# SEP00755AG.net
KiCad netlist of a schematic drawn in Altium Designer
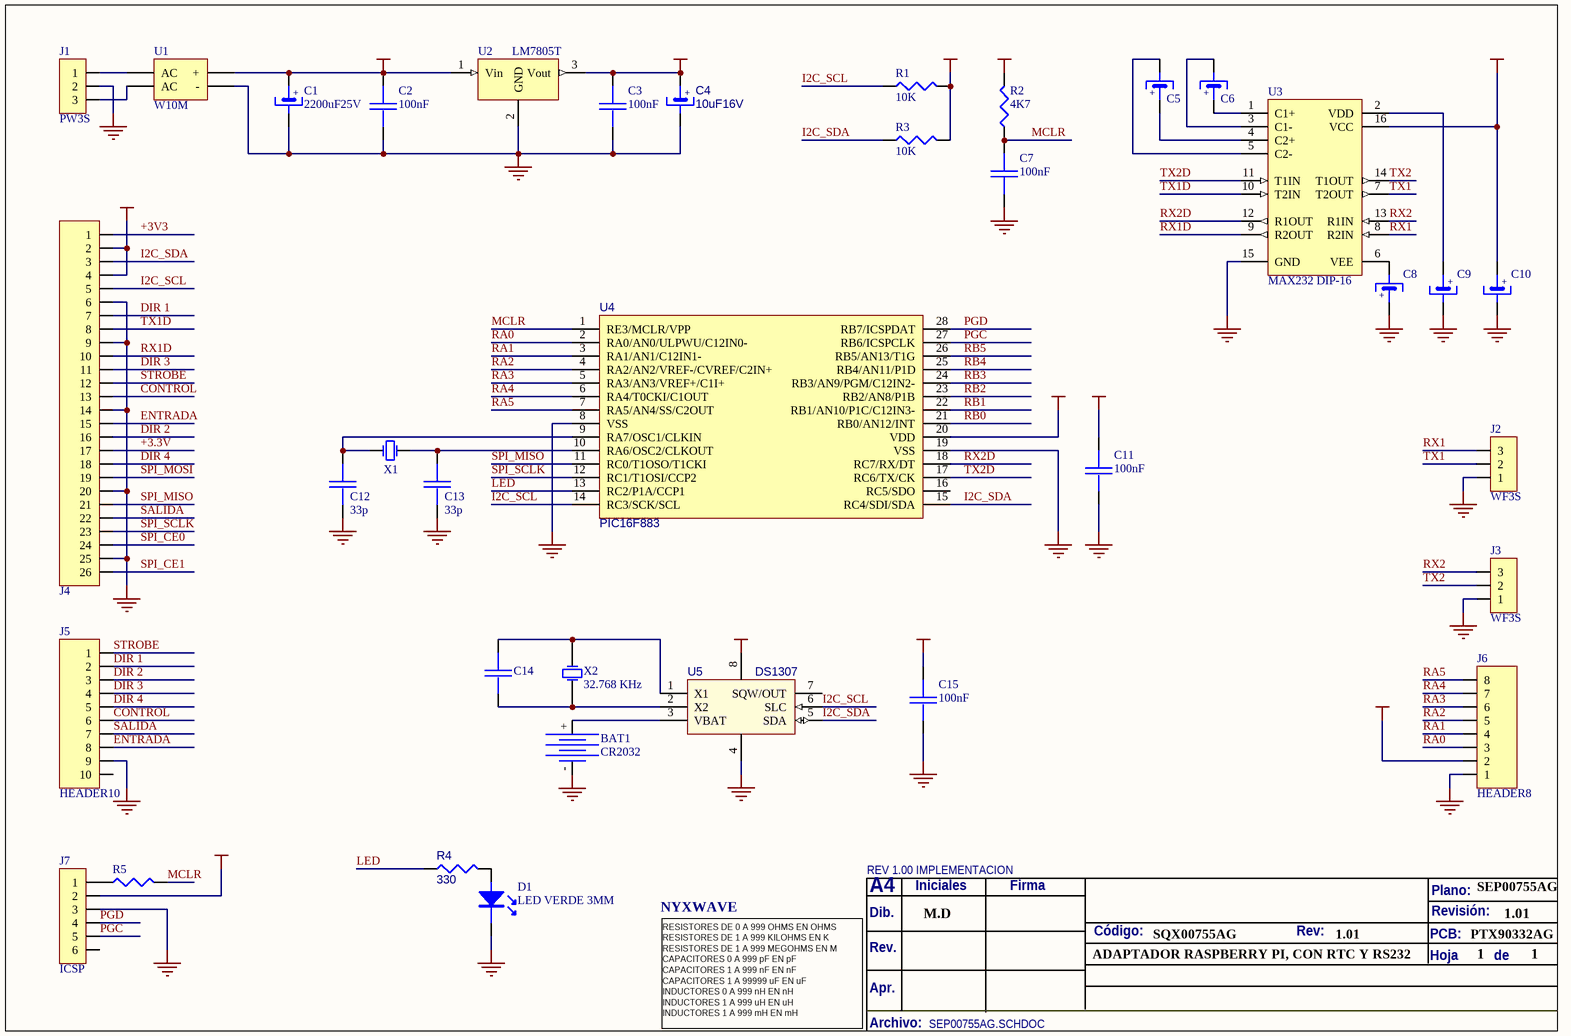
[diagram p0: SEP00755AG.SCHDOC]

(export (version "E")
  (design (tool "Eeschema 10.0.6"))
  (components
    (comp (ref "BAT1")
      (value "CR2032")
      (footprint "CR2032 HOLDER")
      (description "CR2032 BATTERY HOLDER")
      (libsource (lib "ACCESORIOS DE MONTAJE") (part "CR2032 HOLDER"))
    )
    (comp (ref "C1")
      (value "2200uF25V")
      (footprint "CE 7.5/16.0")
      (description "CAPACITOR ELECTROLITICO RADIAL 16X25 mm PASO 7.5 mm +/-20% 85ºC 25V 2200uF")
      (libsource (lib "CAPACITORES ELECTROLITICOS") (part "2200uF25V"))
    )
    (comp (ref "C2")
      (value "100nF")
      (footprint "0805")
      (description "CAPACITOR SMD 0805 X7R  50 V 100 nF")
      (libsource (lib "CAPACITORES SMD0805") (part "100n"))
    )
    (comp (ref "C3")
      (value "100nF")
      (footprint "0805")
      (description "CAPACITOR SMD 0805 X7R  50 V 100 nF")
      (libsource (lib "CAPACITORES SMD0805") (part "100n"))
    )
    (comp (ref "C4")
      (value "10uF16V")
      (footprint "CE 2.5/5.0")
      (description "CAPACITOR ELECTROLITICO RADIAL 5X11mm PASO 2mm 85ªC +/-20 16V 10uF")
      (libsource (lib "CAPACITORES ELECTROLITICOS") (part "10uF16V"))
    )
    (comp (ref "C5")
      (value "10uF50V")
      (footprint "CE 2.5/5.0")
      (description "CAPACITOR ELECTROLITICO RADIAL 5 X11mm PASO 2 mm 85ºC +/-20% 50 V 10 uF")
      (libsource (lib "CAPACITORES ELECTROLITICOS") (part "10uF50V"))
    )
    (comp (ref "C6")
      (value "10uF50V")
      (footprint "CE 2.5/5.0")
      (description "CAPACITOR ELECTROLITICO RADIAL 5 X11mm PASO 2 mm 85ºC +/-20% 50 V 10 uF")
      (libsource (lib "CAPACITORES ELECTROLITICOS") (part "10uF50V"))
    )
    (comp (ref "C7")
      (value "100nF")
      (footprint "0805")
      (description "CAPACITOR SMD 0805 X7R  50 V 100 nF")
      (libsource (lib "CAPACITORES SMD0805") (part "100n"))
    )
    (comp (ref "C8")
      (value "10uF50V")
      (footprint "CE 2.5/5.0")
      (description "CAPACITOR ELECTROLITICO RADIAL 5 X11mm PASO 2 mm 85ºC +/-20% 50 V 10 uF")
      (libsource (lib "CAPACITORES ELECTROLITICOS") (part "10uF50V"))
    )
    (comp (ref "C9")
      (value "10uF50V")
      (footprint "CE 2.5/5.0")
      (description "CAPACITOR ELECTROLITICO RADIAL 5 X11mm PASO 2 mm 85ºC +/-20% 50 V 10 uF")
      (libsource (lib "CAPACITORES ELECTROLITICOS") (part "10uF50V"))
    )
    (comp (ref "C10")
      (value "10uF50V")
      (footprint "CE 2.5/5.0")
      (description "CAPACITOR ELECTROLITICO RADIAL 5 X11mm PASO 2 mm 85ºC +/-20% 50 V 10 uF")
      (libsource (lib "CAPACITORES ELECTROLITICOS") (part "10uF50V"))
    )
    (comp (ref "C11")
      (value "100nF")
      (footprint "0805")
      (description "CAPACITOR SMD 0805 X7R  50 V 100 nF")
      (libsource (lib "CAPACITORES SMD0805") (part "100n"))
    )
    (comp (ref "C12")
      (value "33p")
      (footprint "CAP2.54")
      (description "CAPACITOR PLATE NP0 100V PASO 2.54 mm 33 pF")
      (libsource (lib "CAPACITORES PLATE NP0") (part "33p"))
    )
    (comp (ref "C13")
      (value "33p")
      (footprint "CAP2.54")
      (description "CAPACITOR PLATE NP0 100V PASO 2.54 mm 33 pF")
      (libsource (lib "CAPACITORES PLATE NP0") (part "33p"))
    )
    (comp (ref "C14")
      (value "15p")
      (footprint "CAP2.54")
      (description "CAPACITOR CERAMICO DISCO 2.54 mm  X7R  50V  15pF")
      (libsource (lib "CAPACITORES CERAMICO DISCO") (part "15p"))
    )
    (comp (ref "C15")
      (value "100nF")
      (footprint "0805")
      (description "CAPACITOR SMD 0805 X7R  50 V 100 nF")
      (libsource (lib "CAPACITORES SMD0805") (part "100n"))
    )
    (comp (ref "D1")
      (value "LED VERDE 3MM")
      (footprint "LED 3MM")
      (libsource (lib "DIODOS") (part "LED VERDE 3MM"))
    )
    (comp (ref "J1")
      (value "PW3S")
      (footprint "PW3S")
      (description "PW3S HEADER .156\" RECTO 3 VIAS")
      (libsource (lib "CONECTORES") (part "PW3S"))
    )
    (comp (ref "J2")
      (value "WF3S")
      (footprint "WF3S")
      (description "WF3S HEADER .100\" RECTO 3 VIAS")
      (libsource (lib "CONECTORES") (part "WF3S"))
    )
    (comp (ref "J3")
      (value "WF3S")
      (footprint "WF3S")
      (description "WF3S HEADER .100\" RECTO 3 VIAS")
      (libsource (lib "CONECTORES") (part "WF3S"))
    )
    (comp (ref "J4")
      (value "HEADER26")
      (footprint "IDC26")
      (description "CONECTOR IDC MACHO PCB NO POLARIZADO PASO 2.54 mm RECTO 2X13 VIAS")
      (libsource (lib "CONECTORES") (part "HEADER26"))
    )
    (comp (ref "J5")
      (value "HEADER10")
      (footprint "IDC10")
      (description "CONECTOR IDC MACHO PCB NO POLARIZADO PASO 2.54 mm RECTO 2X5 VIAS")
      (libsource (lib "CONECTORES") (part "HEADER10"))
    )
    (comp (ref "J6")
      (value "HEADER8")
      (footprint "IDC8")
      (description "CONECTOR IDC MACHO PCB NO POLARIZADO PASO 2.54 mm RECTO 2X4 VIAS")
      (libsource (lib "CONECTORES") (part "HEADER8"))
    )
    (comp (ref "J7")
      (value "ICSP")
      (footprint "ICSP")
      (description "TIRA MOLEX 1X6 11MM MACHO RECTA PARA PCB")
      (libsource (lib "CONECTORES") (part "ICSP"))
    )
    (comp (ref "NYXWAVE")
      (value "LOGO NYX")
      (footprint "LOGO_NYX")
      (description "LOGO DE NYXWAVE")
      (libsource (lib "ACCESORIOS DE MONTAJE") (part "LOGO NYXWAVE"))
    )
    (comp (ref "R1")
      (value "10K")
      (footprint "0805")
      (description "RESISTOR SMD0805 0.125 W 5%  10 K OHMS")
      (libsource (lib "RESISTORES SMD0805") (part "10K"))
    )
    (comp (ref "R2")
      (value "4K7")
      (footprint "0805")
      (description "RESISTOR SMD0805 0.125 W 5%  4.7 K OHMS")
      (libsource (lib "RESISTORES SMD0805") (part "4K7"))
    )
    (comp (ref "R3")
      (value "10K")
      (footprint "0805")
      (description "RESISTOR SMD0805 0.125 W 5%  10 K OHMS")
      (libsource (lib "RESISTORES SMD0805") (part "10K"))
    )
    (comp (ref "R4")
      (value "330")
      (footprint "0805")
      (description "RESISTOR SMD0805 0.125 W 5%  330 OHMS")
      (libsource (lib "RESISTORES SMD0805") (part "330"))
    )
    (comp (ref "R5")
      (value "100")
      (footprint "0805")
      (description "RESISTOR SMD0805 0.125 W 5%  100 OHMS")
      (libsource (lib "RESISTORES SMD0805") (part "100"))
    )
    (comp (ref "U1")
      (value "W10M")
      (footprint "CASE22")
      (description "W10M CASE22 CIRC INT RECTIFICADOR PUENTE 1000V 1A")
      (libsource (lib "CIRCUITOS INTEGRADOS DIP") (part "W10M"))
    )
    (comp (ref "U2")
      (value "LM7805T")
      (footprint "TO-220_2")
      (description "LM7805T TO-220 CIRC INT")
      (libsource (lib "CIRCUITOS INTEGRADOS DIP") (part "LM7805T"))
    )
    (comp (ref "U3")
      (value "MAX232 DIP-16")
      (footprint "DIP16")
      (description "MAX232 DIP-16 CIRCUITO INTEGRADO")
      (libsource (lib "Maxim Communication Transceiver") (part "MAX232 DIP-16"))
    )
    (comp (ref "U4")
      (value "PIC16F883")
      (footprint "SOIC 28")
      (description "PIC16F8883 -I/SO SOIC 28 PINES")
      (libsource (lib "CIRCUITOS INTEGRADOS SMD") (part "PIC16F883 SOIC28"))
    )
    (comp (ref "U5")
      (value "DS1307")
      (footprint "SO-8")
      (description "DS1307 SOIC8 CIRCUITO INTEGRADO")
      (libsource (lib "CIRCUITOS INTEGRADOS SMD") (part "DS1307"))
    )
    (comp (ref "X1")
      (value "XL20M-UM5")
      (footprint "UM5")
      (description "XL20M-UM5 CRISTAL DE 20 MHZ 10ppm")
      (libsource (lib "CRISTALES") (part "XL20M-UM5"))
    )
    (comp (ref "X2")
      (value "32.768 KHz")
      (footprint "XTAL ACOSTADO")
      (description "32.768 KHz CRISTAL CILINDRICO")
      (libsource (lib "CRISTALES") (part "32.768 KHz"))
    )
  )
  (nets
    (net (code "1") (name "+5V") (class "Default")
      (node (ref "C10") (pin "1") (pinfunction "1_1") (pintype "passive"))
      (node (ref "C11") (pin "2") (pintype "passive"))
      (node (ref "C15") (pin "2") (pintype "passive"))
      (node (ref "C3") (pin "2") (pintype "passive"))
      (node (ref "C4") (pin "1") (pinfunction "1_1") (pintype "passive"))
      (node (ref "J4") (pin "2") (pinfunction "2_2") (pintype "passive"))
      (node (ref "J4") (pin "4") (pinfunction "4_4") (pintype "passive"))
      (node (ref "J6") (pin "2") (pinfunction "2_2") (pintype "passive"))
      (node (ref "J7") (pin "2") (pinfunction "2_2") (pintype "passive"))
      (node (ref "R1") (pin "2") (pintype "passive"))
      (node (ref "R2") (pin "2") (pintype "passive"))
      (node (ref "R3") (pin "2") (pintype "passive"))
      (node (ref "U2") (pin "3") (pinfunction "Vout_3") (pintype "output"))
      (node (ref "U3") (pin "16") (pinfunction "VCC_16") (pintype "power_in"))
      (node (ref "U4") (pin "20") (pinfunction "VDD_20") (pintype "passive"))
      (node (ref "U5") (pin "8") (pinfunction "VCC_8") (pintype "power_in"))
    )
    (net (code "2") (name "/+3.3V") (class "Default")
      (node (ref "J4") (pin "17") (pinfunction "17_17") (pintype "passive"))
    )
    (net (code "3") (name "/+3V3") (class "Default")
      (node (ref "J4") (pin "1") (pinfunction "1_1") (pintype "passive"))
    )
    (net (code "4") (name "/CONTROL") (class "Default")
      (node (ref "J4") (pin "13") (pinfunction "13_13") (pintype "passive"))
      (node (ref "J5") (pin "6") (pinfunction "6_6") (pintype "passive"))
    )
    (net (code "5") (name "/DIR 1") (class "Default")
      (node (ref "J4") (pin "7") (pinfunction "7_7") (pintype "passive"))
      (node (ref "J5") (pin "2") (pinfunction "2_2") (pintype "passive"))
    )
    (net (code "6") (name "/DIR 2") (class "Default")
      (node (ref "J4") (pin "16") (pinfunction "16_16") (pintype "passive"))
      (node (ref "J5") (pin "3") (pinfunction "3_3") (pintype "passive"))
    )
    (net (code "7") (name "/DIR 3") (class "Default")
      (node (ref "J4") (pin "11") (pinfunction "11_11") (pintype "passive"))
      (node (ref "J5") (pin "4") (pinfunction "4_4") (pintype "passive"))
    )
    (net (code "8") (name "/DIR 4") (class "Default")
      (node (ref "J4") (pin "18") (pinfunction "18_18") (pintype "passive"))
      (node (ref "J5") (pin "5") (pinfunction "5_5") (pintype "passive"))
    )
    (net (code "9") (name "/ENTRADA") (class "Default")
      (node (ref "J4") (pin "15") (pinfunction "15_15") (pintype "passive"))
      (node (ref "J5") (pin "8") (pinfunction "8_8") (pintype "passive"))
    )
    (net (code "10") (name "/I2C_SCL") (class "Default")
      (node (ref "J4") (pin "5") (pinfunction "5_5") (pintype "passive"))
      (node (ref "R1") (pin "1") (pintype "passive"))
      (node (ref "U4") (pin "14") (pinfunction "RC3/SCK/SCL_14") (pintype "passive"))
      (node (ref "U5") (pin "6") (pinfunction "SLC_6") (pintype "input"))
    )
    (net (code "11") (name "/I2C_SDA") (class "Default")
      (node (ref "J4") (pin "3") (pinfunction "3_3") (pintype "passive"))
      (node (ref "R3") (pin "1") (pintype "passive"))
      (node (ref "U4") (pin "15") (pinfunction "RC4/SDI/SDA_15") (pintype "passive"))
      (node (ref "U5") (pin "5") (pinfunction "SDA_5") (pintype "bidirectional"))
    )
    (net (code "12") (name "/LED") (class "Default")
      (node (ref "R4") (pin "1") (pintype "passive"))
      (node (ref "U4") (pin "13") (pinfunction "RC2/P1A/CCP1_13") (pintype "passive"))
    )
    (net (code "13") (name "/MCLR") (class "Default")
      (node (ref "C7") (pin "1") (pintype "passive"))
      (node (ref "R2") (pin "1") (pintype "passive"))
      (node (ref "R5") (pin "1") (pintype "passive"))
      (node (ref "U4") (pin "1") (pinfunction "RE3/MCLR/VPP_1") (pintype "passive"))
    )
    (net (code "14") (name "/PGC") (class "Default")
      (node (ref "J7") (pin "5") (pinfunction "5_5") (pintype "passive"))
      (node (ref "U4") (pin "27") (pinfunction "RB6/ICSPCLK_27") (pintype "passive"))
    )
    (net (code "15") (name "/PGD") (class "Default")
      (node (ref "J7") (pin "4") (pinfunction "4_4") (pintype "passive"))
      (node (ref "U4") (pin "28") (pinfunction "RB7/ICSPDAT_28") (pintype "passive"))
    )
    (net (code "16") (name "/RA0") (class "Default")
      (node (ref "J6") (pin "3") (pinfunction "3_3") (pintype "passive"))
      (node (ref "U4") (pin "2") (pinfunction "RA0/AN0/ULPWU/C12IN0-_2") (pintype "passive"))
    )
    (net (code "17") (name "/RA1") (class "Default")
      (node (ref "J6") (pin "4") (pinfunction "4_4") (pintype "passive"))
      (node (ref "U4") (pin "3") (pinfunction "RA1/AN1/C12IN1-_3") (pintype "passive"))
    )
    (net (code "18") (name "/RA2") (class "Default")
      (node (ref "J6") (pin "5") (pinfunction "5_5") (pintype "passive"))
      (node (ref "U4") (pin "4") (pinfunction "RA2/AN2/VREF-/CVREF/C2IN+_4") (pintype "passive"))
    )
    (net (code "19") (name "/RA3") (class "Default")
      (node (ref "J6") (pin "6") (pinfunction "6_6") (pintype "passive"))
      (node (ref "U4") (pin "5") (pinfunction "RA3/AN3/VREF+/C1I+_5") (pintype "passive"))
    )
    (net (code "20") (name "/RA4") (class "Default")
      (node (ref "J6") (pin "7") (pinfunction "7_7") (pintype "passive"))
      (node (ref "U4") (pin "6") (pinfunction "RA4/T0CKI/C1OUT_6") (pintype "passive"))
    )
    (net (code "21") (name "/RA5") (class "Default")
      (node (ref "J6") (pin "8") (pinfunction "8_8") (pintype "passive"))
      (node (ref "U4") (pin "7") (pinfunction "RA5/AN4/SS/C2OUT_7") (pintype "passive"))
    )
    (net (code "22") (name "/RB0") (class "Default")
      (node (ref "U4") (pin "21") (pinfunction "RB0/AN12/INT_21") (pintype "passive"))
    )
    (net (code "23") (name "/RB1") (class "Default")
      (node (ref "U4") (pin "22") (pinfunction "RB1/AN10/P1C/C12IN3-_22") (pintype "passive"))
    )
    (net (code "24") (name "/RB2") (class "Default")
      (node (ref "U4") (pin "23") (pinfunction "RB2/AN8/P1B_23") (pintype "passive"))
    )
    (net (code "25") (name "/RB3") (class "Default")
      (node (ref "U4") (pin "24") (pinfunction "RB3/AN9/PGM/C12IN2-_24") (pintype "passive"))
    )
    (net (code "26") (name "/RB4") (class "Default")
      (node (ref "U4") (pin "25") (pinfunction "RB4/AN11/P1D_25") (pintype "passive"))
    )
    (net (code "27") (name "/RB5") (class "Default")
      (node (ref "U4") (pin "26") (pinfunction "RB5/AN13/T1G_26") (pintype "passive"))
    )
    (net (code "28") (name "/RX1") (class "Default")
      (node (ref "J2") (pin "3") (pinfunction "3_3") (pintype "passive"))
      (node (ref "U3") (pin "8") (pinfunction "R2IN_8") (pintype "input"))
    )
    (net (code "29") (name "/RX1D") (class "Default")
      (node (ref "J4") (pin "10") (pinfunction "10_10") (pintype "passive"))
      (node (ref "U3") (pin "9") (pinfunction "R2OUT_9") (pintype "output"))
    )
    (net (code "30") (name "/RX2") (class "Default")
      (node (ref "J3") (pin "3") (pinfunction "3_3") (pintype "passive"))
      (node (ref "U3") (pin "13") (pinfunction "R1IN_13") (pintype "input"))
    )
    (net (code "31") (name "/RX2D") (class "Default")
      (node (ref "U3") (pin "12") (pinfunction "R1OUT_12") (pintype "output"))
      (node (ref "U4") (pin "18") (pinfunction "RC7/RX/DT_18") (pintype "passive"))
    )
    (net (code "32") (name "/SALIDA") (class "Default")
      (node (ref "J4") (pin "22") (pinfunction "22_22") (pintype "passive"))
      (node (ref "J5") (pin "7") (pinfunction "7_7") (pintype "passive"))
    )
    (net (code "33") (name "/SPI_CE0") (class "Default")
      (node (ref "J4") (pin "24") (pinfunction "24_24") (pintype "passive"))
    )
    (net (code "34") (name "/SPI_CE1") (class "Default")
      (node (ref "J4") (pin "26") (pinfunction "26_26") (pintype "passive"))
    )
    (net (code "35") (name "/SPI_MISO") (class "Default")
      (node (ref "J4") (pin "21") (pinfunction "21_21") (pintype "passive"))
      (node (ref "U4") (pin "11") (pinfunction "RC0/T1OSO/T1CKI_11") (pintype "passive"))
    )
    (net (code "36") (name "/SPI_MOSI") (class "Default")
      (node (ref "J4") (pin "19") (pinfunction "19_19") (pintype "passive"))
    )
    (net (code "37") (name "/SPI_SCLK") (class "Default")
      (node (ref "J4") (pin "23") (pinfunction "23_23") (pintype "passive"))
      (node (ref "U4") (pin "12") (pinfunction "RC1/T1OSI/CCP2_12") (pintype "passive"))
    )
    (net (code "38") (name "/STROBE") (class "Default")
      (node (ref "J4") (pin "12") (pinfunction "12_12") (pintype "passive"))
      (node (ref "J5") (pin "1") (pinfunction "1_1") (pintype "passive"))
    )
    (net (code "39") (name "/TX1") (class "Default")
      (node (ref "J2") (pin "2") (pinfunction "2_2") (pintype "passive"))
      (node (ref "U3") (pin "7") (pinfunction "T2OUT_7") (pintype "output"))
    )
    (net (code "40") (name "/TX1D") (class "Default")
      (node (ref "J4") (pin "8") (pinfunction "8_8") (pintype "passive"))
      (node (ref "U3") (pin "10") (pinfunction "T2IN_10") (pintype "input"))
    )
    (net (code "41") (name "/TX2") (class "Default")
      (node (ref "J3") (pin "2") (pinfunction "2_2") (pintype "passive"))
      (node (ref "U3") (pin "14") (pinfunction "T1OUT_14") (pintype "output"))
    )
    (net (code "42") (name "/TX2D") (class "Default")
      (node (ref "U3") (pin "11") (pinfunction "T1IN_11") (pintype "input"))
      (node (ref "U4") (pin "17") (pinfunction "RC6/TX/CK_17") (pintype "passive"))
    )
    (net (code "43") (name "GND") (class "Default")
      (node (ref "BAT1") (pin "-") (pinfunction "-_-") (pintype "passive"))
      (node (ref "C1") (pin "2") (pinfunction "2_2") (pintype "passive"))
      (node (ref "C10") (pin "2") (pinfunction "2_2") (pintype "passive"))
      (node (ref "C11") (pin "1") (pintype "passive"))
      (node (ref "C12") (pin "1") (pintype "passive"))
      (node (ref "C13") (pin "1") (pintype "passive"))
      (node (ref "C15") (pin "1") (pintype "passive"))
      (node (ref "C2") (pin "1") (pintype "passive"))
      (node (ref "C3") (pin "1") (pintype "passive"))
      (node (ref "C4") (pin "2") (pinfunction "2_2") (pintype "passive"))
      (node (ref "C7") (pin "2") (pintype "passive"))
      (node (ref "C8") (pin "1") (pinfunction "1_1") (pintype "passive"))
      (node (ref "C9") (pin "2") (pinfunction "2_2") (pintype "passive"))
      (node (ref "D1") (pin "K") (pinfunction "K_K") (pintype "passive"))
      (node (ref "J1") (pin "2") (pinfunction "2_2") (pintype "passive"))
      (node (ref "J2") (pin "1") (pinfunction "1_1") (pintype "passive"))
      (node (ref "J3") (pin "1") (pinfunction "1_1") (pintype "passive"))
      (node (ref "J4") (pin "14") (pinfunction "14_14") (pintype "passive"))
      (node (ref "J4") (pin "20") (pinfunction "20_20") (pintype "passive"))
      (node (ref "J4") (pin "25") (pinfunction "25_25") (pintype "passive"))
      (node (ref "J4") (pin "6") (pinfunction "6_6") (pintype "passive"))
      (node (ref "J4") (pin "9") (pinfunction "9_9") (pintype "passive"))
      (node (ref "J5") (pin "9") (pinfunction "9_9") (pintype "passive"))
      (node (ref "J6") (pin "1") (pinfunction "1_1") (pintype "passive"))
      (node (ref "J7") (pin "3") (pinfunction "3_3") (pintype "passive"))
      (node (ref "U1") (pin "3") (pinfunction "-_3") (pintype "passive"))
      (node (ref "U2") (pin "2") (pinfunction "GND_2") (pintype "passive"))
      (node (ref "U3") (pin "15") (pinfunction "GND_15") (pintype "power_in"))
      (node (ref "U4") (pin "19") (pinfunction "VSS_19") (pintype "passive"))
      (node (ref "U4") (pin "8") (pinfunction "VSS_8") (pintype "passive"))
      (node (ref "U5") (pin "4") (pinfunction "VSS_4") (pintype "passive"))
    )
    (net (code "44") (name "Net-(D1-PadA)") (class "Default")
      (node (ref "D1") (pin "A") (pinfunction "A_A") (pintype "passive"))
      (node (ref "R4") (pin "2") (pintype "passive"))
    )
    (net (code "45") (name "Net-(J1-Pad1)") (class "Default")
      (node (ref "J1") (pin "1") (pinfunction "1_1") (pintype "passive"))
      (node (ref "U1") (pin "2") (pinfunction "AC_2") (pintype "passive"))
    )
    (net (code "46") (name "Net-(J1-Pad3)") (class "Default")
      (node (ref "J1") (pin "3") (pinfunction "3_3") (pintype "passive"))
      (node (ref "U1") (pin "4") (pinfunction "AC_4") (pintype "passive"))
    )
    (net (code "47") (name "Net-(J7-Pad1)") (class "Default")
      (node (ref "J7") (pin "1") (pinfunction "1_1") (pintype "passive"))
      (node (ref "R5") (pin "2") (pintype "passive"))
    )
    (net (code "48") (name "Net-(U3-C1+)") (class "Default")
      (node (ref "C6") (pin "1") (pinfunction "1_1") (pintype "passive"))
      (node (ref "U3") (pin "1") (pinfunction "C1+_1") (pintype "passive"))
    )
    (net (code "49") (name "Net-(U3-C1-)") (class "Default")
      (node (ref "C6") (pin "2") (pinfunction "2_2") (pintype "passive"))
      (node (ref "U3") (pin "3") (pinfunction "C1-_3") (pintype "passive"))
    )
    (net (code "50") (name "Net-(U3-C2+)") (class "Default")
      (node (ref "C5") (pin "1") (pinfunction "1_1") (pintype "passive"))
      (node (ref "U3") (pin "4") (pinfunction "C2+_4") (pintype "passive"))
    )
    (net (code "51") (name "Net-(U3-C2-)") (class "Default")
      (node (ref "C5") (pin "2") (pinfunction "2_2") (pintype "passive"))
      (node (ref "U3") (pin "5") (pinfunction "C2-_5") (pintype "passive"))
    )
    (net (code "52") (name "Net-(U3-VDD)") (class "Default")
      (node (ref "C9") (pin "1") (pinfunction "1_1") (pintype "passive"))
      (node (ref "U3") (pin "2") (pinfunction "VDD_2") (pintype "power_in"))
    )
    (net (code "53") (name "Net-(U3-VEE)") (class "Default")
      (node (ref "C8") (pin "2") (pinfunction "2_2") (pintype "passive"))
      (node (ref "U3") (pin "6") (pinfunction "VEE_6") (pintype "power_in"))
    )
    (net (code "54") (name "Net-(U4-RA6{slash}OSC2{slash}CLKOUT)") (class "Default")
      (node (ref "C13") (pin "2") (pintype "passive"))
      (node (ref "U4") (pin "10") (pinfunction "RA6/OSC2/CLKOUT_10") (pintype "passive"))
      (node (ref "X1") (pin "2") (pinfunction "OSC2_2") (pintype "passive"))
    )
    (net (code "55") (name "Net-(U4-RA7{slash}OSC1{slash}CLKIN)") (class "Default")
      (node (ref "C12") (pin "2") (pintype "passive"))
      (node (ref "U4") (pin "9") (pinfunction "RA7/OSC1/CLKIN_9") (pintype "passive"))
      (node (ref "X1") (pin "1") (pinfunction "OSC1_1") (pintype "passive"))
    )
    (net (code "56") (name "Net-(U5-VBAT)") (class "Default")
      (node (ref "BAT1") (pin "+") (pinfunction "+_+") (pintype "passive"))
      (node (ref "U5") (pin "3") (pinfunction "VBAT_3") (pintype "passive"))
    )
    (net (code "57") (name "Net-(U5-X1)") (class "Default")
      (node (ref "C14") (pin "2") (pintype "passive"))
      (node (ref "U5") (pin "1") (pinfunction "X1_1") (pintype "passive"))
      (node (ref "X2") (pin "2") (pinfunction "OSC2_2") (pintype "passive"))
    )
    (net (code "58") (name "Net-(U5-X2)") (class "Default")
      (node (ref "C14") (pin "1") (pintype "passive"))
      (node (ref "U5") (pin "2") (pinfunction "X2_2") (pintype "passive"))
      (node (ref "X2") (pin "1") (pinfunction "OSC1_1") (pintype "passive"))
    )
    (net (code "59") (name "VCC") (class "Default")
      (node (ref "C1") (pin "1") (pinfunction "1_1") (pintype "passive"))
      (node (ref "C2") (pin "2") (pintype "passive"))
      (node (ref "U1") (pin "1") (pinfunction "+_1") (pintype "passive"))
      (node (ref "U2") (pin "1") (pinfunction "Vin_1") (pintype "input"))
    )
    (net (code "60") (name "unconnected-(J5-Pad10)") (class "Default")
      (node (ref "J5") (pin "10") (pinfunction "10_10") (pintype "passive"))
    )
    (net (code "61") (name "unconnected-(J7-Pad6)") (class "Default")
      (node (ref "J7") (pin "6") (pinfunction "6_6") (pintype "passive"))
    )
    (net (code "62") (name "unconnected-(U4-RC5{slash}SDO-Pad16)") (class "Default")
      (node (ref "U4") (pin "16") (pinfunction "RC5/SDO_16") (pintype "passive"))
    )
    (net (code "63") (name "unconnected-(U5-SQW{slash}OUT-Pad7)") (class "Default")
      (node (ref "U5") (pin "7") (pinfunction "SQW/OUT_7") (pintype "passive"))
    )
  )
)
